# FMC_top.net
KiCad netlist of a schematic drawn in Altium Designer
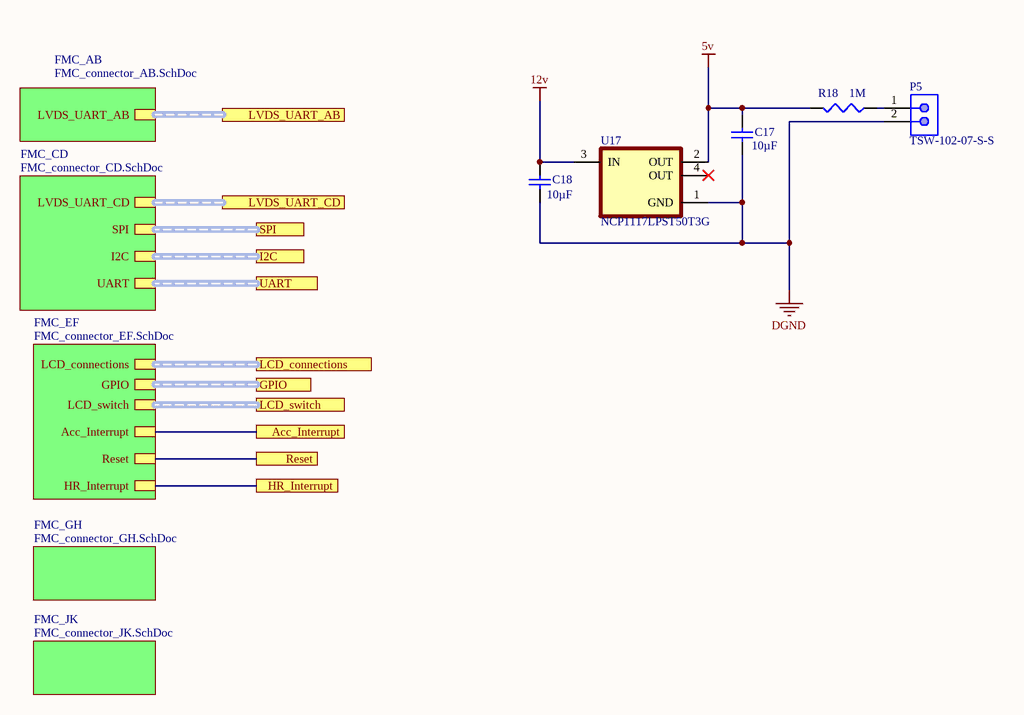
[diagram p0: FMC_top.SchDoc]

(export (version "E")
  (design (tool "Eeschema 10.0.6"))
  (components
    (comp (ref "C17")
      (value "C1608X5R1A106K080AC")
      (footprint "CAPC1608X90X20LL10")
      (description "Chip Capacitor, 10 uF, +/- 10%, 10 V, -55 to 85 degC, 0603 (1608 Metric), RoHS, Tape and Reel")
      (fields
        (field (name "PCN PART NUMBER") "MLCCPartNumberChange30/Nov/2012")
        (field (name "TOLERANCE") "±10%")
        (field (name "CAPACITANCE") "10µF")
      )
      (libsource (lib "Passives") (part "CMP-2000-04979-1"))
    )
    (comp (ref "C18")
      (value "C1608X5R1A106K080AC")
      (footprint "CAPC1608X90X20LL10")
      (description "Chip Capacitor, 10 uF, +/- 10%, 10 V, -55 to 85 degC, 0603 (1608 Metric), RoHS, Tape and Reel")
      (fields
        (field (name "PCN PART NUMBER") "MLCCPartNumberChange30/Nov/2012")
        (field (name "TOLERANCE") "±10%")
        (field (name "CAPACITANCE") "10µF")
      )
      (libsource (lib "Passives") (part "CMP-2000-04979-1"))
    )
    (comp (ref "P5")
      (value "TSW-102-07-S-S")
      (footprint "SMTC-TSW-102-07-S-S")
      (fields (field (name "MANUFACTURER") "Samtec"))
      (libsource (lib "Altium Content Vault") (part "CN-1P-M-R2"))
    )
    (comp (ref "R18")
      (value "1M")
      (footprint "J1-0603")
      (description "Resistor")
      (fields (field (name "Comment") "Res3") (field (name "PUBLISHER") "Altium Limited"))
      (libsource (lib "Miscellaneous Devices") (part "Res3"))
    )
    (comp (ref "U17")
      (value "NCP1117LPST50T3G")
      (footprint "SOT230P700X180-4N")
      (description "Linear Voltage Regulator IC 1 Output 1A SOT-223")
      (fields
        (field (name "DIGI-KEY_PART_NUMBER") "NCP1117LPST50T3GOSCT-ND")
        (field (name "MF") "ON Semiconductor")
      )
      (libsource (lib "Components") (part "NCP1117LPST50T3G"))
    )
  )
  (nets
    (net (code "20") (name "5v") (class "Default")
      (node (ref "C17") (pin "2") (pinfunction "2_2") (pintype "passive"))
      (node (ref "R18") (pin "2") (pinfunction "2_2") (pintype "passive"))
      (node (ref "U17") (pin "2") (pinfunction "OUT_2") (pintype "passive"))
    )
    (net (code "21") (name "12v") (class "Default")
      (node (ref "C18") (pin "2") (pinfunction "2_2") (pintype "passive"))
      (node (ref "U17") (pin "3") (pinfunction "IN_3") (pintype "passive"))
    )
    (net (code "22") (name "DGND") (class "Default")
      (node (ref "C17") (pin "1") (pinfunction "1_1") (pintype "passive"))
      (node (ref "C18") (pin "1") (pinfunction "1_1") (pintype "passive"))
      (node (ref "P5") (pin "2") (pinfunction "2_2") (pintype "passive"))
      (node (ref "U17") (pin "1") (pinfunction "GND_1") (pintype "power_in"))
    )
    (net (code "23") (name "Net-(P5-Pad1)") (class "Default")
      (node (ref "P5") (pin "1") (pinfunction "1_1") (pintype "passive"))
      (node (ref "R18") (pin "1") (pinfunction "1_1") (pintype "passive"))
    )
    (net (code "24") (name "unconnected-(U17-OUT-Pad4)") (class "Default")
      (node (ref "U17") (pin "4") (pinfunction "OUT_4") (pintype "passive+no_connect"))
    )
  )
)
